# PWM_board_1_2.net
KiCad netlist of a schematic drawn in EAGLE
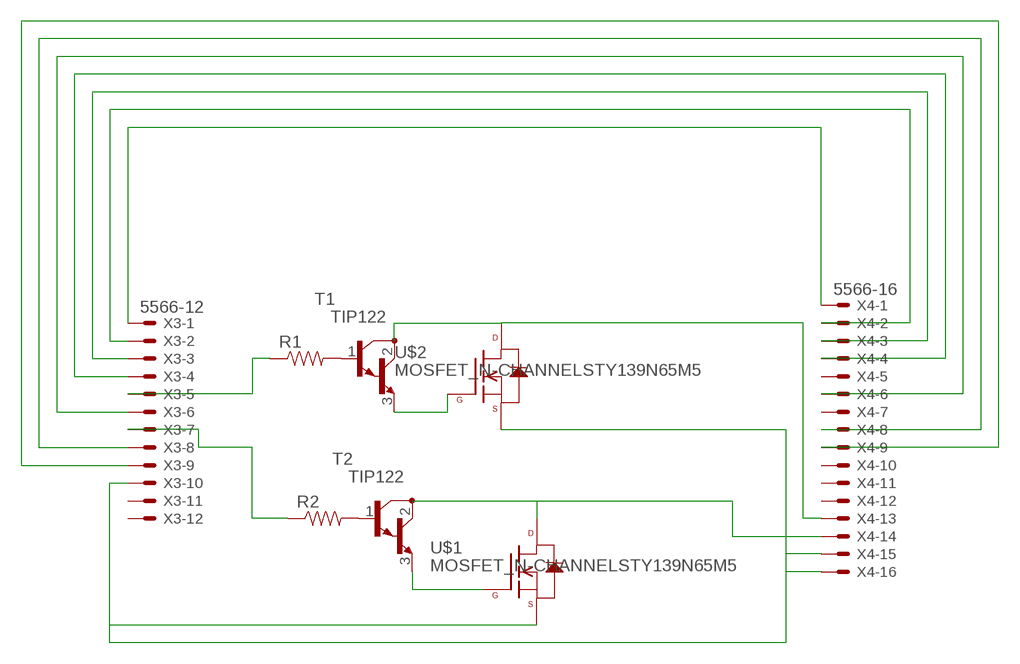
[diagram p0: schematic, sheet 1]

(export (version "E")
  (design (tool "Eeschema 10.0.6"))
  (components
    (comp (ref "R1")
      (value "RESISTORPTH-1/2W")
      (footprint "eagle-import:AXIAL-0.5")
      (libsource (lib "eagle-import") (part "RESISTORPTH-1/2W"))
    )
    (comp (ref "R2")
      (value "RESISTORPTH-1/2W")
      (footprint "eagle-import:AXIAL-0.5")
      (libsource (lib "eagle-import") (part "RESISTORPTH-1/2W"))
    )
    (comp (ref "T1")
      (value "TIP122")
      (footprint "eagle-import:TO220")
      (libsource (lib "eagle-import") (part "TIP122"))
    )
    (comp (ref "T2")
      (value "TIP122")
      (footprint "eagle-import:TO220")
      (libsource (lib "eagle-import") (part "TIP122"))
    )
    (comp (ref "U$1")
      (value "MOSFET_N-CHANNELSTY139N65M5")
      (footprint "eagle-import:TO-264_MAX247")
      (libsource (lib "eagle-import") (part "MOSFET_N-CHANNELSTY139N65M5"))
    )
    (comp (ref "U$2")
      (value "MOSFET_N-CHANNELSTY139N65M5")
      (footprint "eagle-import:TO-264_MAX247")
      (libsource (lib "eagle-import") (part "MOSFET_N-CHANNELSTY139N65M5"))
    )
    (comp (ref "X3")
      (value "5566-12")
      (footprint "eagle-import:5566-12")
      (libsource (lib "eagle-import") (part "5566-12"))
    )
    (comp (ref "X4")
      (value "5566-16")
      (footprint "eagle-import:5566-16")
      (libsource (lib "eagle-import") (part "5566-16"))
    )
  )
  (nets
    (net (code "1") (name "Net-(R1-1)") (class "Default")
      (node (ref "R1") (pin "P$1") (pinfunction "1_P$1") (pintype "passive"))
      (node (ref "X3") (pin "5") (pinfunction "S_5") (pintype "passive"))
    )
    (net (code "2") (name "Net-(R1-2)") (class "Default")
      (node (ref "R1") (pin "P$2") (pinfunction "2_P$2") (pintype "passive"))
      (node (ref "T1") (pin "1") (pinfunction "B_1") (pintype "passive"))
    )
    (net (code "3") (name "Net-(R2-1)") (class "Default")
      (node (ref "R2") (pin "P$1") (pinfunction "1_P$1") (pintype "passive"))
      (node (ref "X3") (pin "7") (pinfunction "S_7") (pintype "passive"))
    )
    (net (code "4") (name "Net-(R2-2)") (class "Default")
      (node (ref "R2") (pin "P$2") (pinfunction "2_P$2") (pintype "passive"))
      (node (ref "T2") (pin "1") (pinfunction "B_1") (pintype "passive"))
    )
    (net (code "5") (name "Net-(T1-C)") (class "Default")
      (node (ref "T1") (pin "2") (pinfunction "C_2") (pintype "passive"))
      (node (ref "U$2") (pin "P2") (pinfunction "DRAIN_P2") (pintype "passive"))
      (node (ref "X4") (pin "13") (pinfunction "S_13") (pintype "passive"))
    )
    (net (code "6") (name "Net-(T1-E)") (class "Default")
      (node (ref "T1") (pin "3") (pinfunction "E_3") (pintype "passive"))
      (node (ref "U$2") (pin "P1") (pinfunction "GATE_P1") (pintype "passive"))
    )
    (net (code "7") (name "Net-(T2-C)") (class "Default")
      (node (ref "T2") (pin "2") (pinfunction "C_2") (pintype "passive"))
      (node (ref "U$1") (pin "P2") (pinfunction "DRAIN_P2") (pintype "passive"))
      (node (ref "X4") (pin "14") (pinfunction "S_14") (pintype "passive"))
    )
    (net (code "8") (name "Net-(T2-E)") (class "Default")
      (node (ref "T2") (pin "3") (pinfunction "E_3") (pintype "passive"))
      (node (ref "U$1") (pin "P1") (pinfunction "GATE_P1") (pintype "passive"))
    )
    (net (code "9") (name "Net-(U$1-SOURCE)") (class "Default")
      (node (ref "U$1") (pin "P3") (pinfunction "SOURCE_P3") (pintype "passive"))
      (node (ref "U$2") (pin "P3") (pinfunction "SOURCE_P3") (pintype "passive"))
      (node (ref "X3") (pin "10") (pinfunction "S_10") (pintype "passive"))
      (node (ref "X4") (pin "15") (pinfunction "S_15") (pintype "passive"))
      (node (ref "X4") (pin "16") (pinfunction "S_16") (pintype "passive"))
    )
    (net (code "10") (name "Net-(X3A-S)") (class "Default")
      (node (ref "X3") (pin "1") (pinfunction "S_1") (pintype "passive"))
      (node (ref "X4") (pin "1") (pinfunction "S_1") (pintype "passive"))
    )
    (net (code "11") (name "Net-(X3E-S)") (class "Default")
      (node (ref "X3") (pin "2") (pinfunction "S_2") (pintype "passive"))
      (node (ref "X4") (pin "2") (pinfunction "S_2") (pintype "passive"))
    )
    (net (code "12") (name "Net-(X3F-S)") (class "Default")
      (node (ref "X3") (pin "3") (pinfunction "S_3") (pintype "passive"))
      (node (ref "X4") (pin "3") (pinfunction "S_3") (pintype "passive"))
    )
    (net (code "13") (name "Net-(X3G-S)") (class "Default")
      (node (ref "X3") (pin "4") (pinfunction "S_4") (pintype "passive"))
      (node (ref "X4") (pin "4") (pinfunction "S_4") (pintype "passive"))
    )
    (net (code "14") (name "Net-(X3I-S)") (class "Default")
      (node (ref "X3") (pin "6") (pinfunction "S_6") (pintype "passive"))
      (node (ref "X4") (pin "6") (pinfunction "S_6") (pintype "passive"))
    )
    (net (code "15") (name "Net-(X3K-S)") (class "Default")
      (node (ref "X3") (pin "8") (pinfunction "S_8") (pintype "passive"))
      (node (ref "X4") (pin "8") (pinfunction "S_8") (pintype "passive"))
    )
    (net (code "16") (name "Net-(X3L-S)") (class "Default")
      (node (ref "X3") (pin "9") (pinfunction "S_9") (pintype "passive"))
      (node (ref "X4") (pin "9") (pinfunction "S_9") (pintype "passive"))
    )
    (net (code "17") (name "unconnected-(X3C-S-Pad11)") (class "Default")
      (node (ref "X3") (pin "11") (pinfunction "S_11") (pintype "passive"))
    )
    (net (code "18") (name "unconnected-(X3D-S-Pad12)") (class "Default")
      (node (ref "X3") (pin "12") (pinfunction "S_12") (pintype "passive"))
    )
    (net (code "19") (name "unconnected-(X4B-S-Pad10)") (class "Default")
      (node (ref "X4") (pin "10") (pinfunction "S_10") (pintype "passive"))
    )
    (net (code "20") (name "unconnected-(X4C-S-Pad11)") (class "Default")
      (node (ref "X4") (pin "11") (pinfunction "S_11") (pintype "passive"))
    )
    (net (code "21") (name "unconnected-(X4D-S-Pad12)") (class "Default")
      (node (ref "X4") (pin "12") (pinfunction "S_12") (pintype "passive"))
    )
    (net (code "22") (name "unconnected-(X4L-S-Pad5)") (class "Default")
      (node (ref "X4") (pin "5") (pinfunction "S_5") (pintype "passive"))
    )
    (net (code "23") (name "unconnected-(X4N-S-Pad7)") (class "Default")
      (node (ref "X4") (pin "7") (pinfunction "S_7") (pintype "passive"))
    )
  )
)
